# OpenBook.net
KiCad netlist of a schematic drawn in EAGLE
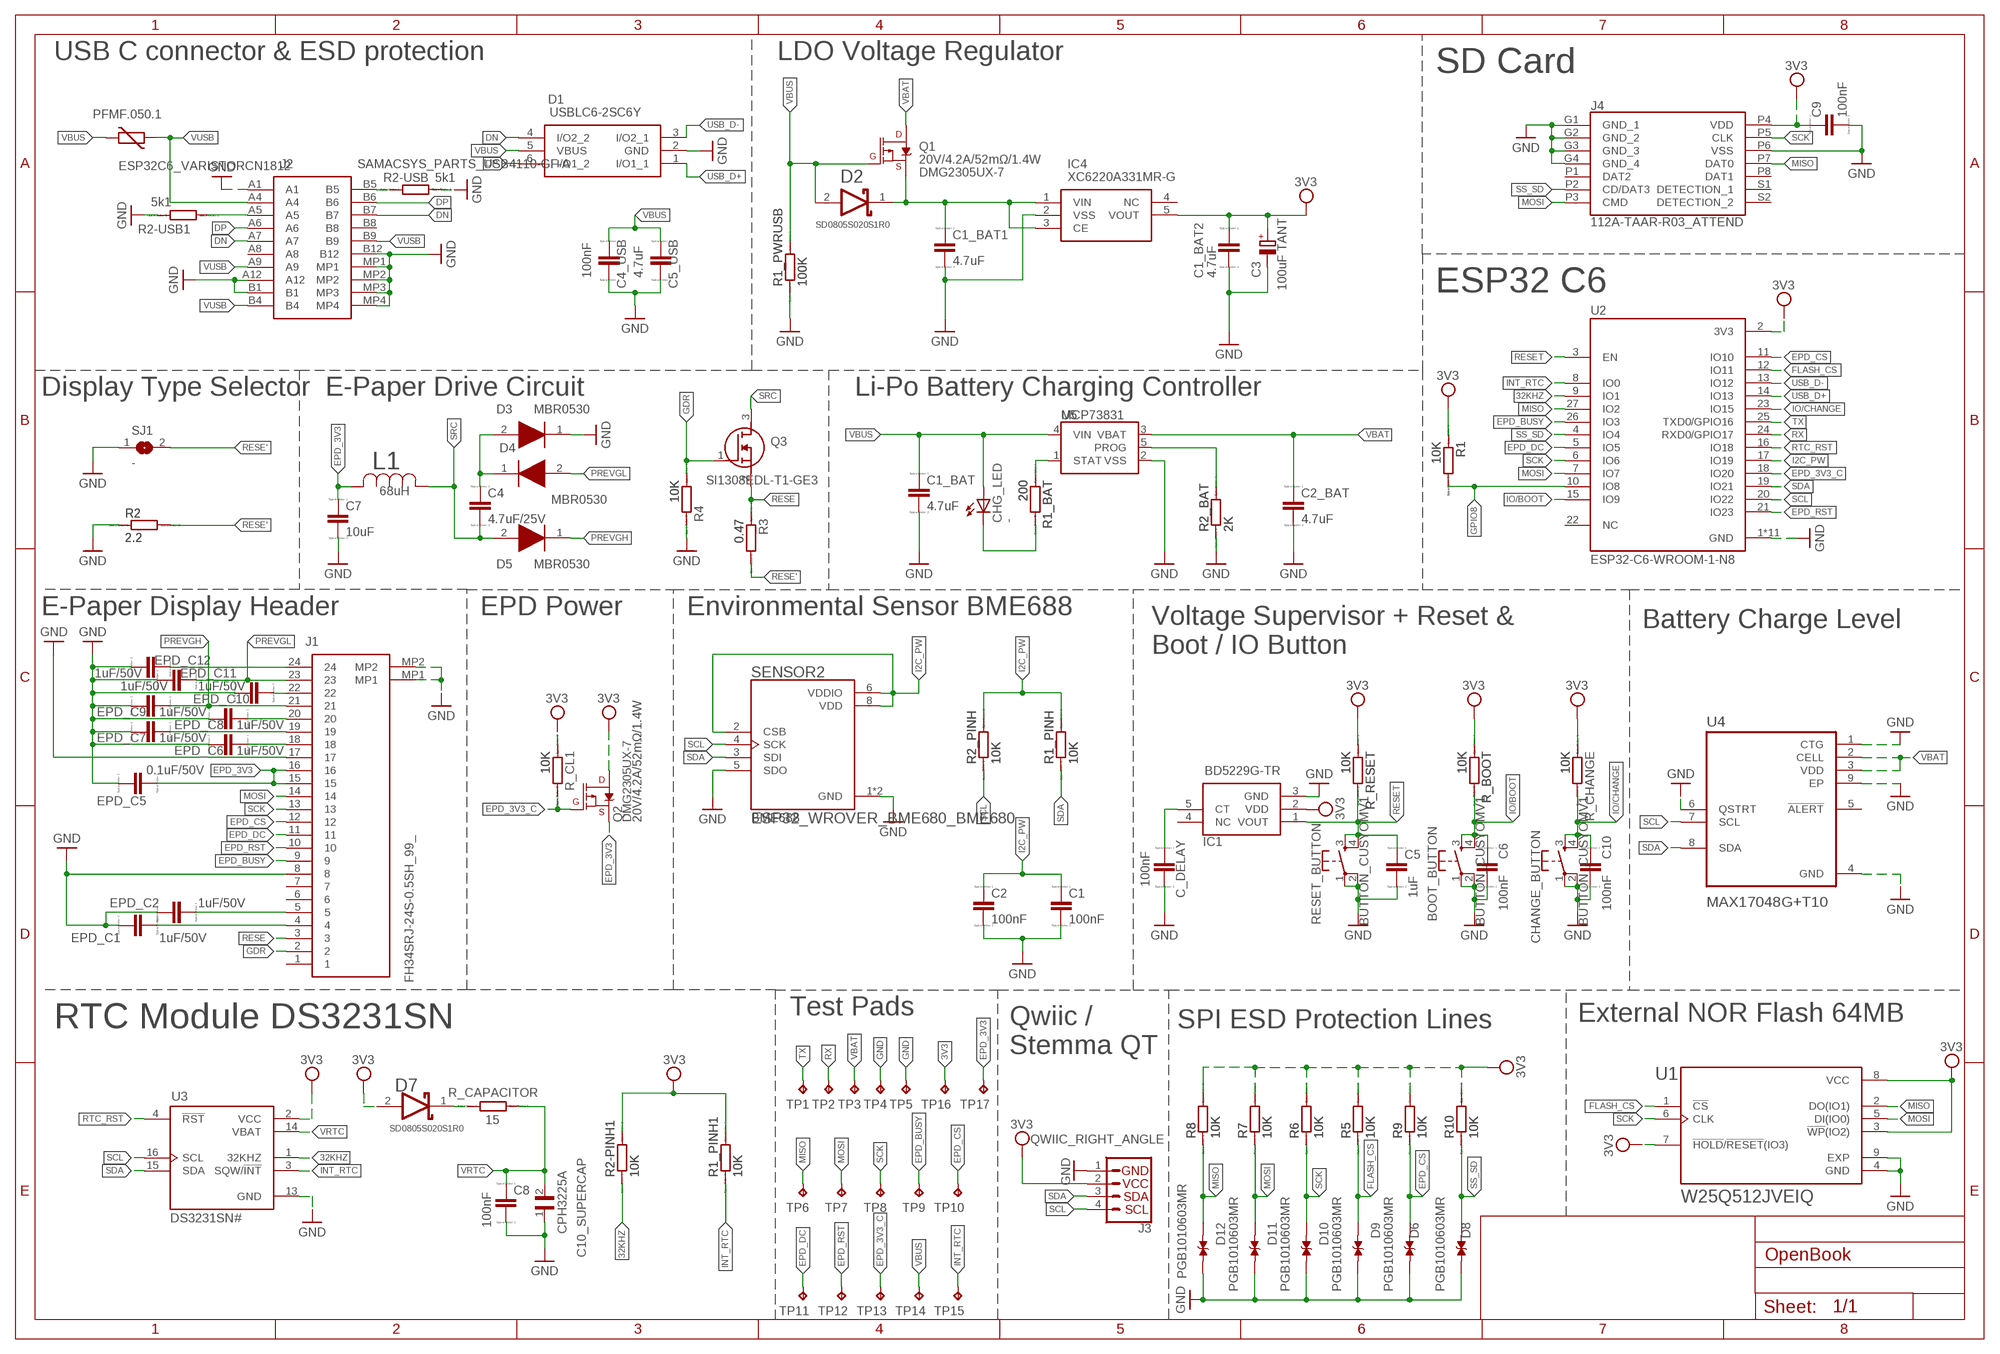
[diagram p0: schematic, sheet 1]

(export (version "E")
  (design (tool "Eeschema 10.0.6"))
  (components
    (comp (ref "BOOT_BUTTON")
      (value "BUTTON_CUSYOMV1")
      (footprint "eagle-import:MYBUTTON")
      (libsource (lib "eagle-import") (part "BUTTON_CUSYOMV1"))
    )
    (comp (ref "C1")
      (value "100nF")
      (footprint "eagle-import:EAGLE-LTSPICE_C0402")
      (libsource (lib "eagle-import") (part "EAGLE-LTSPICE_CC0402"))
    )
    (comp (ref "C1_BAT")
      (value "4.7uF")
      (footprint "eagle-import:EAGLE-LTSPICE_C0402")
      (libsource (lib "eagle-import") (part "EAGLE-LTSPICE_CC0402"))
    )
    (comp (ref "C1_BAT1")
      (value "4.7uF")
      (footprint "eagle-import:EAGLE-LTSPICE_C0402")
      (libsource (lib "eagle-import") (part "EAGLE-LTSPICE_CC0402"))
    )
    (comp (ref "C1_BAT2")
      (value "4.7uF")
      (footprint "eagle-import:EAGLE-LTSPICE_C0402")
      (libsource (lib "eagle-import") (part "EAGLE-LTSPICE_CC0402"))
    )
    (comp (ref "C2")
      (value "100nF")
      (footprint "eagle-import:EAGLE-LTSPICE_C0402")
      (libsource (lib "eagle-import") (part "EAGLE-LTSPICE_CC0402"))
    )
    (comp (ref "C2_BAT")
      (value "4.7uF")
      (footprint "eagle-import:EAGLE-LTSPICE_C0402")
      (libsource (lib "eagle-import") (part "EAGLE-LTSPICE_CC0402"))
    )
    (comp (ref "C3")
      (value "100uF TANT")
      (footprint "eagle-import:RCL_CT3528")
      (libsource (lib "eagle-import") (part "RCL_CPOL-EUCT3528"))
    )
    (comp (ref "C4")
      (value "4.7uF/25V")
      (footprint "eagle-import:EAGLE-LTSPICE_C0402")
      (libsource (lib "eagle-import") (part "EAGLE-LTSPICE_CC0402"))
    )
    (comp (ref "C4_USB")
      (value "100nF")
      (footprint "eagle-import:EAGLE-LTSPICE_C0402")
      (libsource (lib "eagle-import") (part "EAGLE-LTSPICE_CC0402"))
    )
    (comp (ref "C5")
      (value "1uF")
      (footprint "eagle-import:EAGLE-LTSPICE_C0402")
      (libsource (lib "eagle-import") (part "EAGLE-LTSPICE_CC0402"))
    )
    (comp (ref "C5_USB")
      (value "4.7uF")
      (footprint "eagle-import:EAGLE-LTSPICE_C0402")
      (libsource (lib "eagle-import") (part "EAGLE-LTSPICE_CC0402"))
    )
    (comp (ref "C6")
      (value "100nF")
      (footprint "eagle-import:EAGLE-LTSPICE_C0402")
      (libsource (lib "eagle-import") (part "EAGLE-LTSPICE_CC0402"))
    )
    (comp (ref "C7")
      (value "10uF")
      (footprint "eagle-import:EAGLE-LTSPICE_C0402")
      (libsource (lib "eagle-import") (part "EAGLE-LTSPICE_CC0402"))
    )
    (comp (ref "C8")
      (value "100nF")
      (footprint "eagle-import:EAGLE-LTSPICE_C0402")
      (libsource (lib "eagle-import") (part "EAGLE-LTSPICE_CC0402"))
    )
    (comp (ref "C9")
      (value "100nF")
      (footprint "eagle-import:EAGLE-LTSPICE_C0402")
      (libsource (lib "eagle-import") (part "EAGLE-LTSPICE_CC0402"))
    )
    (comp (ref "C10")
      (value "100nF")
      (footprint "eagle-import:EAGLE-LTSPICE_C0402")
      (libsource (lib "eagle-import") (part "EAGLE-LTSPICE_CC0402"))
    )
    (comp (ref "C10_SUPERCAP")
      (value "CPH3225A")
      (footprint "eagle-import:CAPCP3225X100N")
      (fields (field (name "MF") "Seiko Instruments"))
      (libsource (lib "eagle-import") (part "CPH3225A"))
    )
    (comp (ref "CHANGE_BUTTON")
      (value "BUTTON_CUSYOMV1")
      (footprint "eagle-import:MYBUTTON")
      (libsource (lib "eagle-import") (part "BUTTON_CUSYOMV1"))
    )
    (comp (ref "CHG_LED")
      (value "-")
      (footprint "eagle-import:ADAFRUIT_CHIP-LED0603")
      (libsource (lib "eagle-import") (part "ADAFRUIT_LEDCHIP-LED0603"))
    )
    (comp (ref "C_DELAY")
      (value "100nF")
      (footprint "eagle-import:EAGLE-LTSPICE_C0402")
      (libsource (lib "eagle-import") (part "EAGLE-LTSPICE_CC0402"))
    )
    (comp (ref "D1")
      (value "USBLC6-2SC6Y")
      (footprint "eagle-import:SOT95P280X145-6N")
      (fields (field (name "MF") "STMicroelectronics"))
      (libsource (lib "eagle-import") (part "USBLC6-2SC6Y"))
    )
    (comp (ref "D2")
      (value "SD0805S020S1R0")
      (footprint "eagle-import:ESP32_WROVER_AVX---SD0805S020S1R0_AVX_SD0805S020S1R0_0")
      (fields
        (field (name "DIGIKEY_PART_NUMBER") "478-7800-1-ND")
        (field (name "MF") "AVX")
        (field (name "MOUSER_PART_NUMBER") "581-SD0805S020S1R0")
        (field (name "VALUE_COPY") "SD0805S020S1R0")
      )
      (libsource (lib "eagle-import") (part "ESP32_WROVER_AVX---SD0805S020S1R0_AVX_SD0805S020S1R0_0_0AVX_SD0805S020S1R0_0_0"))
    )
    (comp (ref "D3")
      (value "MBR0530")
      (footprint "eagle-import:SOD3716X135N")
      (fields (field (name "MF") "ON Semiconductor"))
      (libsource (lib "eagle-import") (part "MBR0530"))
    )
    (comp (ref "D4")
      (value "MBR0530")
      (footprint "eagle-import:SOD3716X135N")
      (fields (field (name "MF") "ON Semiconductor"))
      (libsource (lib "eagle-import") (part "MBR0530"))
    )
    (comp (ref "D5")
      (value "MBR0530")
      (footprint "eagle-import:SOD3716X135N")
      (fields (field (name "MF") "ON Semiconductor"))
      (libsource (lib "eagle-import") (part "MBR0530"))
    )
    (comp (ref "D6")
      (value "PGB1010603MR")
      (footprint "eagle-import:DIOC1608X36N")
      (fields (field (name "MF") "Littelfuse Inc."))
      (libsource (lib "eagle-import") (part "PGB1010603MR"))
    )
    (comp (ref "D7")
      (value "ESP32_WROVER_AVX---SD0805S020S1R0_AVX_SD0805S020S1R0_0_0AVX_SD0805S020S1R0_0_0")
      (footprint "eagle-import:ESP32_WROVER_AVX---SD0805S020S1R0_AVX_SD0805S020S1R0_0")
      (fields
        (field (name "DIGIKEY_PART_NUMBER") "478-7800-1-ND")
        (field (name "MF") "AVX")
        (field (name "MOUSER_PART_NUMBER") "581-SD0805S020S1R0")
        (field (name "VALUE_COPY") "SD0805S020S1R0")
      )
      (libsource (lib "eagle-import") (part "ESP32_WROVER_AVX---SD0805S020S1R0_AVX_SD0805S020S1R0_0_0AVX_SD0805S020S1R0_0_0"))
    )
    (comp (ref "D8")
      (value "PGB1010603MR")
      (footprint "eagle-import:DIOC1608X36N")
      (fields (field (name "MF") "Littelfuse Inc."))
      (libsource (lib "eagle-import") (part "PGB1010603MR"))
    )
    (comp (ref "D9")
      (value "PGB1010603MR")
      (footprint "eagle-import:DIOC1608X36N")
      (fields (field (name "MF") "Littelfuse Inc."))
      (libsource (lib "eagle-import") (part "PGB1010603MR"))
    )
    (comp (ref "D10")
      (value "PGB1010603MR")
      (footprint "eagle-import:DIOC1608X36N")
      (fields (field (name "MF") "Littelfuse Inc."))
      (libsource (lib "eagle-import") (part "PGB1010603MR"))
    )
    (comp (ref "D11")
      (value "PGB1010603MR")
      (footprint "eagle-import:DIOC1608X36N")
      (fields (field (name "MF") "Littelfuse Inc."))
      (libsource (lib "eagle-import") (part "PGB1010603MR"))
    )
    (comp (ref "D12")
      (value "PGB1010603MR")
      (footprint "eagle-import:DIOC1608X36N")
      (fields (field (name "MF") "Littelfuse Inc."))
      (libsource (lib "eagle-import") (part "PGB1010603MR"))
    )
    (comp (ref "EPD_C1")
      (value "1uF/50V")
      (footprint "eagle-import:EAGLE-LTSPICE_C0402")
      (libsource (lib "eagle-import") (part "EAGLE-LTSPICE_CC0402"))
    )
    (comp (ref "EPD_C2")
      (value "1uF/50V")
      (footprint "eagle-import:EAGLE-LTSPICE_C0402")
      (libsource (lib "eagle-import") (part "EAGLE-LTSPICE_CC0402"))
    )
    (comp (ref "EPD_C5")
      (value "0.1uF/50V")
      (footprint "eagle-import:EAGLE-LTSPICE_C0402")
      (libsource (lib "eagle-import") (part "EAGLE-LTSPICE_CC0402"))
    )
    (comp (ref "EPD_C6")
      (value "1uF/50V")
      (footprint "eagle-import:EAGLE-LTSPICE_C0402")
      (libsource (lib "eagle-import") (part "EAGLE-LTSPICE_CC0402"))
    )
    (comp (ref "EPD_C7")
      (value "1uF/50V")
      (footprint "eagle-import:EAGLE-LTSPICE_C0402")
      (libsource (lib "eagle-import") (part "EAGLE-LTSPICE_CC0402"))
    )
    (comp (ref "EPD_C8")
      (value "1uF/50V")
      (footprint "eagle-import:EAGLE-LTSPICE_C0402")
      (libsource (lib "eagle-import") (part "EAGLE-LTSPICE_CC0402"))
    )
    (comp (ref "EPD_C9")
      (value "1uF/50V")
      (footprint "eagle-import:EAGLE-LTSPICE_C0402")
      (libsource (lib "eagle-import") (part "EAGLE-LTSPICE_CC0402"))
    )
    (comp (ref "EPD_C10")
      (value "1uF/50V")
      (footprint "eagle-import:EAGLE-LTSPICE_C0402")
      (libsource (lib "eagle-import") (part "EAGLE-LTSPICE_CC0402"))
    )
    (comp (ref "EPD_C11")
      (value "1uF/50V")
      (footprint "eagle-import:EAGLE-LTSPICE_C0402")
      (libsource (lib "eagle-import") (part "EAGLE-LTSPICE_CC0402"))
    )
    (comp (ref "EPD_C12")
      (value "1uF/50V")
      (footprint "eagle-import:EAGLE-LTSPICE_C0402")
      (libsource (lib "eagle-import") (part "EAGLE-LTSPICE_CC0402"))
    )
    (comp (ref "IC1")
      (value "BD5229G-TR")
      (footprint "eagle-import:SOT95P280X125-5N")
      (fields (field (name "MOUSER_PART_NUMBER") "755-BD5229G-TR"))
      (libsource (lib "eagle-import") (part "BD5229G-TR"))
    )
    (comp (ref "IC4")
      (value "XC6220A331MR-G")
      (footprint "eagle-import:SOT95P280X120-5N")
      (fields (field (name "MOUSER_PART_NUMBER") "865-XC6220A331MR-G"))
      (libsource (lib "eagle-import") (part "XC6220A331MR-G"))
    )
    (comp (ref "J1")
      (value "FH34SRJ-24S-0.5SH_99_")
      (footprint "eagle-import:FH34SRJ24S05SH99")
      (fields
        (field (name "MANUFACTURER_PART_NUMBER") "FH34SRJ-24S-0.5SH(99)")
        (field (name "MOUSER_PART_NUMBER") "798-FH34SRJ24S05SH99")
      )
      (libsource (lib "eagle-import") (part "FH34SRJ-24S-0.5SH_99_"))
    )
    (comp (ref "J2")
      (value "SAMACSYS_PARTS_USB4110-GF-A")
      (footprint "eagle-import:SAMACSYS_PARTS_USB4110GFA")
      (fields
        (field (name "MANUFACTURER_PART_NUMBER") "USB4110-GF-A")
        (field (name "MOUSER_PART_NUMBER") "640-USB4110-GF-A")
      )
      (libsource (lib "eagle-import") (part "SAMACSYS_PARTS_USB4110-GF-A"))
    )
    (comp (ref "J3")
      (value "QWIIC_RIGHT_ANGLE")
      (footprint "eagle-import:JST04_1MM_RA")
      (libsource (lib "eagle-import") (part "QWIIC_CONNECTORJS-1MM"))
    )
    (comp (ref "J4")
      (value "112A-TAAR-R03_ATTEND")
      (footprint "eagle-import:112ATAARR03ATTEND")
      (fields (field (name "MANUFACTURER_PART_NUMBER") "112A-TAAR-R03 ATTEND"))
      (libsource (lib "eagle-import") (part "112A-TAAR-R03_ATTEND"))
    )
    (comp (ref "L1")
      (value "68uH")
      (footprint "eagle-import:IND_4828-WE-TPC_WRE")
      (fields
        (field (name "MANUFACTURER_PART_NUMBER") "744043680")
        (field (name "COPYRIGHT") "Copyright (C) 2024 Ultra Librarian. All rights reserved.")
      )
      (libsource (lib "eagle-import") (part "744043680IND_4828-WE-TPC_WRE"))
    )
    (comp (ref "PFMF.050.1")
      (value "ESP32C6_VARISTORCN1812")
      (footprint "eagle-import:ESP32C6_VARISTOR_CT_CN1812")
      (libsource (lib "eagle-import") (part "ESP32C6_VARISTORCN1812"))
    )
    (comp (ref "Q1")
      (value "20V/4.2A/52mΩ/1.4W")
      (footprint "eagle-import:ESP32_WROVER_SPARKFUN-DISCRETESEMI_SOT23-3")
      (fields (field (name "COMP_NAME") "DMG2305UX-7"))
      (libsource (lib "eagle-import") (part "ESP32_WROVER_SPARKFUN-DISCRETESEMI_MOSFET_PCH-DMG2305UX-7"))
    )
    (comp (ref "Q2")
      (value "20V/4.2A/52mΩ/1.4W")
      (footprint "eagle-import:ESP32_WROVER_SPARKFUN-DISCRETESEMI_SOT23-3")
      (fields (field (name "MP") "DMG2305UX-7"))
      (libsource (lib "eagle-import") (part "ESP32_WROVER_SPARKFUN-DISCRETESEMI_MOSFET_PCH-DMG2305UX-7"))
    )
    (comp (ref "Q3")
      (value "SI1308EDL-T1-GE3")
      (footprint "eagle-import:SOT65P210X110-3N")
      (fields (field (name "MF") "Vishay Siliconix"))
      (libsource (lib "eagle-import") (part "SI1308EDL-T1-GE3"))
    )
    (comp (ref "R1")
      (value "10K")
      (footprint "eagle-import:ESP32_WROVER_EAGLE-LTSPICE_R0402")
      (libsource (lib "eagle-import") (part "ESP32_WROVER_EAGLE-LTSPICE_RR0402"))
    )
    (comp (ref "R1_BAT")
      (value "200")
      (footprint "eagle-import:ESP32_WROVER_EAGLE-LTSPICE_R0402")
      (libsource (lib "eagle-import") (part "ESP32_WROVER_EAGLE-LTSPICE_RR0402"))
    )
    (comp (ref "R1_PINH")
      (value "10K")
      (footprint "eagle-import:ESP32_WROVER_EAGLE-LTSPICE_R0402")
      (libsource (lib "eagle-import") (part "ESP32_WROVER_EAGLE-LTSPICE_RR0402"))
    )
    (comp (ref "R1_PINH1")
      (value "10K")
      (footprint "eagle-import:ESP32_WROVER_EAGLE-LTSPICE_R0402")
      (libsource (lib "eagle-import") (part "ESP32_WROVER_EAGLE-LTSPICE_RR0402"))
    )
    (comp (ref "R1_PWRUSB")
      (value "100K")
      (footprint "eagle-import:ESP32_WROVER_EAGLE-LTSPICE_R0402")
      (libsource (lib "eagle-import") (part "ESP32_WROVER_EAGLE-LTSPICE_RR0402"))
    )
    (comp (ref "R2")
      (value "2.2")
      (footprint "eagle-import:ESP32_WROVER_EAGLE-LTSPICE_R0402")
      (libsource (lib "eagle-import") (part "ESP32_WROVER_EAGLE-LTSPICE_RR0402"))
    )
    (comp (ref "R2-PINH1")
      (value "10K")
      (footprint "eagle-import:ESP32_WROVER_EAGLE-LTSPICE_R0402")
      (libsource (lib "eagle-import") (part "ESP32_WROVER_EAGLE-LTSPICE_RR0402"))
    )
    (comp (ref "R2-USB")
      (value "5k1")
      (footprint "eagle-import:ESP32_WROVER_EAGLE-LTSPICE_R0402")
      (libsource (lib "eagle-import") (part "ESP32_WROVER_EAGLE-LTSPICE_RR0402"))
    )
    (comp (ref "R2-USB1")
      (value "5k1")
      (footprint "eagle-import:ESP32_WROVER_EAGLE-LTSPICE_R0402")
      (libsource (lib "eagle-import") (part "ESP32_WROVER_EAGLE-LTSPICE_RR0402"))
    )
    (comp (ref "R2_BAT")
      (value "2K")
      (footprint "eagle-import:ESP32_WROVER_EAGLE-LTSPICE_R0402")
      (libsource (lib "eagle-import") (part "ESP32_WROVER_EAGLE-LTSPICE_RR0402"))
    )
    (comp (ref "R2_PINH")
      (value "10K")
      (footprint "eagle-import:ESP32_WROVER_EAGLE-LTSPICE_R0402")
      (libsource (lib "eagle-import") (part "ESP32_WROVER_EAGLE-LTSPICE_RR0402"))
    )
    (comp (ref "R3")
      (value "0.47")
      (footprint "eagle-import:ESP32_WROVER_EAGLE-LTSPICE_R0402")
      (libsource (lib "eagle-import") (part "ESP32_WROVER_EAGLE-LTSPICE_RR0402"))
    )
    (comp (ref "R4")
      (value "10K")
      (footprint "eagle-import:ESP32_WROVER_EAGLE-LTSPICE_R0402")
      (libsource (lib "eagle-import") (part "ESP32_WROVER_EAGLE-LTSPICE_RR0402"))
    )
    (comp (ref "R5")
      (value "10K")
      (footprint "eagle-import:ESP32_WROVER_EAGLE-LTSPICE_R0402")
      (libsource (lib "eagle-import") (part "ESP32_WROVER_EAGLE-LTSPICE_RR0402"))
    )
    (comp (ref "R6")
      (value "10K")
      (footprint "eagle-import:ESP32_WROVER_EAGLE-LTSPICE_R0402")
      (libsource (lib "eagle-import") (part "ESP32_WROVER_EAGLE-LTSPICE_RR0402"))
    )
    (comp (ref "R7")
      (value "10K")
      (footprint "eagle-import:ESP32_WROVER_EAGLE-LTSPICE_R0402")
      (libsource (lib "eagle-import") (part "ESP32_WROVER_EAGLE-LTSPICE_RR0402"))
    )
    (comp (ref "R8")
      (value "10K")
      (footprint "eagle-import:ESP32_WROVER_EAGLE-LTSPICE_R0402")
      (libsource (lib "eagle-import") (part "ESP32_WROVER_EAGLE-LTSPICE_RR0402"))
    )
    (comp (ref "R9")
      (value "10K")
      (footprint "eagle-import:ESP32_WROVER_EAGLE-LTSPICE_R0402")
      (libsource (lib "eagle-import") (part "ESP32_WROVER_EAGLE-LTSPICE_RR0402"))
    )
    (comp (ref "R10")
      (value "10K")
      (footprint "eagle-import:ESP32_WROVER_EAGLE-LTSPICE_R0402")
      (libsource (lib "eagle-import") (part "ESP32_WROVER_EAGLE-LTSPICE_RR0402"))
    )
    (comp (ref "RESET_BUTTON")
      (value "BUTTON_CUSYOMV1")
      (footprint "eagle-import:MYBUTTON")
      (libsource (lib "eagle-import") (part "BUTTON_CUSYOMV1"))
    )
    (comp (ref "R_BOOT")
      (value "10K")
      (footprint "eagle-import:ESP32_WROVER_EAGLE-LTSPICE_R0402")
      (libsource (lib "eagle-import") (part "ESP32_WROVER_EAGLE-LTSPICE_RR0402"))
    )
    (comp (ref "R_CAPACITOR")
      (value "15")
      (footprint "eagle-import:ESP32_WROVER_EAGLE-LTSPICE_R0402")
      (libsource (lib "eagle-import") (part "ESP32_WROVER_EAGLE-LTSPICE_RR0402"))
    )
    (comp (ref "R_CHANGE")
      (value "10K")
      (footprint "eagle-import:ESP32_WROVER_EAGLE-LTSPICE_R0402")
      (libsource (lib "eagle-import") (part "ESP32_WROVER_EAGLE-LTSPICE_RR0402"))
    )
    (comp (ref "R_CL1")
      (value "10K")
      (footprint "eagle-import:ESP32_WROVER_EAGLE-LTSPICE_R0402")
      (libsource (lib "eagle-import") (part "ESP32_WROVER_EAGLE-LTSPICE_RR0402"))
    )
    (comp (ref "R_RESET")
      (value "10K")
      (footprint "eagle-import:ESP32_WROVER_EAGLE-LTSPICE_R0402")
      (libsource (lib "eagle-import") (part "ESP32_WROVER_EAGLE-LTSPICE_RR0402"))
    )
    (comp (ref "SENSOR2")
      (value "ESP32_WROVER_BME680_BME680")
      (footprint "eagle-import:ESP32_WROVER_BME680_PSON80P300X300X100-8N")
      (fields
        (field (name "MF") "Bosch Sensortec")
        (field (name "MP") "BME680")
        (field (name "NEW_MP") "BME688")
      )
      (libsource (lib "eagle-import") (part "ESP32_WROVER_BME680_BME680"))
    )
    (comp (ref "SJ1") (value "-") (footprint "eagle-import:SJ") (libsource (lib "eagle-import") (part "SJ")))
    (comp (ref "TP1")
      (value "TPTP20R")
      (footprint "eagle-import:TP20R")
      (libsource (lib "eagle-import") (part "TPTP20R"))
    )
    (comp (ref "TP2")
      (value "TPTP20R")
      (footprint "eagle-import:TP20R")
      (libsource (lib "eagle-import") (part "TPTP20R"))
    )
    (comp (ref "TP3")
      (value "TPTP20R")
      (footprint "eagle-import:TP20R")
      (libsource (lib "eagle-import") (part "TPTP20R"))
    )
    (comp (ref "TP4")
      (value "TPTP20R")
      (footprint "eagle-import:TP20R")
      (libsource (lib "eagle-import") (part "TPTP20R"))
    )
    (comp (ref "TP5")
      (value "TPTP20R")
      (footprint "eagle-import:TP20R")
      (libsource (lib "eagle-import") (part "TPTP20R"))
    )
    (comp (ref "TP6")
      (value "TPTP20R")
      (footprint "eagle-import:TP20R")
      (libsource (lib "eagle-import") (part "TPTP20R"))
    )
    (comp (ref "TP7")
      (value "TPTP20R")
      (footprint "eagle-import:TP20R")
      (libsource (lib "eagle-import") (part "TPTP20R"))
    )
    (comp (ref "TP8")
      (value "TPTP20R")
      (footprint "eagle-import:TP20R")
      (libsource (lib "eagle-import") (part "TPTP20R"))
    )
    (comp (ref "TP9")
      (value "TPTP20R")
      (footprint "eagle-import:TP20R")
      (libsource (lib "eagle-import") (part "TPTP20R"))
    )
    (comp (ref "TP10")
      (value "TPTP20R")
      (footprint "eagle-import:TP20R")
      (libsource (lib "eagle-import") (part "TPTP20R"))
    )
    (comp (ref "TP11")
      (value "TPTP20R")
      (footprint "eagle-import:TP20R")
      (libsource (lib "eagle-import") (part "TPTP20R"))
    )
    (comp (ref "TP12")
      (value "TPTP20R")
      (footprint "eagle-import:TP20R")
      (libsource (lib "eagle-import") (part "TPTP20R"))
    )
    (comp (ref "TP13")
      (value "TPTP20R")
      (footprint "eagle-import:TP20R")
      (libsource (lib "eagle-import") (part "TPTP20R"))
    )
    (comp (ref "TP14")
      (value "TPTP20R")
      (footprint "eagle-import:TP20R")
      (libsource (lib "eagle-import") (part "TPTP20R"))
    )
    (comp (ref "TP15")
      (value "TPTP20R")
      (footprint "eagle-import:TP20R")
      (libsource (lib "eagle-import") (part "TPTP20R"))
    )
    (comp (ref "TP16")
      (value "TPTP20R")
      (footprint "eagle-import:TP20R")
      (libsource (lib "eagle-import") (part "TPTP20R"))
    )
    (comp (ref "TP17")
      (value "TPTP20R")
      (footprint "eagle-import:TP20R")
      (libsource (lib "eagle-import") (part "TPTP20R"))
    )
    (comp (ref "U1")
      (value "W25Q512JVEIQ")
      (footprint "eagle-import:SON127P600X800X80-9N")
      (fields (field (name "MF") "Winbond Electronics"))
      (libsource (lib "eagle-import") (part "W25Q512JVEIQ"))
    )
    (comp (ref "U2")
      (value "ESP32-C6-WROOM-1-N8")
      (footprint "eagle-import:XCVR_ESP32-C6-WROOM-1-N8")
      (fields (field (name "MF") "Espressif Systems"))
      (libsource (lib "eagle-import") (part "ESP32-C6-WROOM-1-N8"))
    )
    (comp (ref "U3")
      (value "DS3231SN#")
      (footprint "eagle-import:SOIC127P1032X265-16N")
      (fields (field (name "MF") "Analog Devices"))
      (libsource (lib "eagle-import") (part "DS3231SN#"))
    )
    (comp (ref "U4")
      (value "MAX17048G+T10")
      (footprint "eagle-import:SON50P200X200X80-9N")
      (fields (field (name "MF") "Analog Devices"))
      (libsource (lib "eagle-import") (part "MAX17048G+T10"))
    )
    (comp (ref "U5")
      (value "MCP73831")
      (footprint "eagle-import:ESP32_WROVER_SPARKFUN-IC-POWER_SOT23-5")
      (libsource (lib "eagle-import") (part "ESP32_WROVER_SPARKFUN-IC-POWER_MCP73831"))
    )
  )
  (nets
    (net (code "1") (name "3V3") (class "Default")
      (node (ref "C1_BAT2") (pin "1") (pinfunction "1_1") (pintype "passive"))
      (node (ref "C3") (pin "+") (pinfunction "+_+") (pintype "passive"))
      (node (ref "C9") (pin "1") (pinfunction "1_1") (pintype "passive"))
      (node (ref "D7") (pin "2") (pinfunction "ANODE_2") (pintype "bidirectional"))
      (node (ref "IC1") (pin "2") (pinfunction "VDD_2") (pintype "bidirectional"))
      (node (ref "IC4") (pin "5") (pinfunction "VOUT_5") (pintype "bidirectional"))
      (node (ref "J3") (pin "2") (pinfunction "2_2") (pintype "power_in"))
      (node (ref "J4") (pin "P4") (pinfunction "VDD_P4") (pintype "bidirectional"))
      (node (ref "Q2") (pin "3") (pinfunction "D_3") (pintype "bidirectional"))
      (node (ref "R1") (pin "1") (pinfunction "1_1") (pintype "passive"))
      (node (ref "R10") (pin "2") (pinfunction "2_2") (pintype "passive"))
      (node (ref "R1_PINH1") (pin "2") (pinfunction "2_2") (pintype "passive"))
      (node (ref "R2-PINH1") (pin "2") (pinfunction "2_2") (pintype "passive"))
      (node (ref "R5") (pin "2") (pinfunction "2_2") (pintype "passive"))
      (node (ref "R6") (pin "2") (pinfunction "2_2") (pintype "passive"))
      (node (ref "R7") (pin "2") (pinfunction "2_2") (pintype "passive"))
      (node (ref "R8") (pin "2") (pinfunction "2_2") (pintype "passive"))
      (node (ref "R9") (pin "2") (pinfunction "2_2") (pintype "passive"))
      (node (ref "R_BOOT") (pin "1") (pinfunction "1_1") (pintype "passive"))
      (node (ref "R_CHANGE") (pin "1") (pinfunction "1_1") (pintype "passive"))
      (node (ref "R_CL1") (pin "1") (pinfunction "1_1") (pintype "passive"))
      (node (ref "R_RESET") (pin "1") (pinfunction "1_1") (pintype "passive"))
      (node (ref "TP16") (pin "TP") (pinfunction "TP_TP") (pintype "input"))
      (node (ref "U1") (pin "3") (pinfunction "~{WP}(IO2)_3") (pintype "bidirectional"))
      (node (ref "U1") (pin "7") (pinfunction "~{HOLD}/~{RESET}(IO3)_7") (pintype "bidirectional"))
      (node (ref "U1") (pin "8") (pinfunction "VCC_8") (pintype "power_in"))
      (node (ref "U2") (pin "2") (pinfunction "3V3_2") (pintype "power_in"))
      (node (ref "U3") (pin "2") (pinfunction "VCC_2") (pintype "power_in"))
    )
    (net (code "2") (name "32KHZ") (class "Default")
      (node (ref "R2-PINH1") (pin "1") (pinfunction "1_1") (pintype "passive"))
      (node (ref "U2") (pin "9") (pinfunction "IO1_9") (pintype "bidirectional"))
      (node (ref "U3") (pin "1") (pinfunction "32KHZ_1") (pintype "output"))
    )
    (net (code "3") (name "DN") (class "Default")
      (node (ref "D1") (pin "4") (pinfunction "I/O2_2_4") (pintype "bidirectional"))
      (node (ref "J2") (pin "A7") (pinfunction "A7_A7") (pintype "bidirectional"))
      (node (ref "J2") (pin "B7") (pinfunction "B7_B7") (pintype "bidirectional"))
    )
    (net (code "4") (name "DP") (class "Default")
      (node (ref "D1") (pin "6") (pinfunction "I/O1_2_6") (pintype "bidirectional"))
      (node (ref "J2") (pin "A6") (pinfunction "A6_A6") (pintype "bidirectional"))
      (node (ref "J2") (pin "B6") (pinfunction "B6_B6") (pintype "bidirectional"))
    )
    (net (code "5") (name "EPD_3V3") (class "Default")
      (node (ref "C7") (pin "1") (pinfunction "1_1") (pintype "passive"))
      (node (ref "EPD_C5") (pin "1") (pinfunction "1_1") (pintype "passive"))
      (node (ref "J1") (pin "15") (pinfunction "15_15") (pintype "bidirectional"))
      (node (ref "J1") (pin "16") (pinfunction "16_16") (pintype "bidirectional"))
      (node (ref "L1") (pin "2") (pinfunction "2_2") (pintype "passive"))
      (node (ref "Q2") (pin "2") (pinfunction "S_2") (pintype "bidirectional"))
      (node (ref "TP17") (pin "TP") (pinfunction "TP_TP") (pintype "input"))
    )
    (net (code "6") (name "EPD_3V3_C") (class "Default")
      (node (ref "Q2") (pin "1") (pinfunction "G_1") (pintype "bidirectional"))
      (node (ref "R_CL1") (pin "2") (pinfunction "2_2") (pintype "passive"))
      (node (ref "TP13") (pin "TP") (pinfunction "TP_TP") (pintype "input"))
      (node (ref "U2") (pin "18") (pinfunction "IO20_18") (pintype "bidirectional"))
    )
    (net (code "7") (name "EPD_BUSY") (class "Default")
      (node (ref "J1") (pin "9") (pinfunction "9_9") (pintype "bidirectional"))
      (node (ref "TP9") (pin "TP") (pinfunction "TP_TP") (pintype "input"))
      (node (ref "U2") (pin "26") (pinfunction "IO3_26") (pintype "bidirectional"))
    )
    (net (code "8") (name "EPD_CS") (class "Default")
      (node (ref "D6") (pin "1") (pinfunction "1_1") (pintype "passive"))
      (node (ref "J1") (pin "12") (pinfunction "12_12") (pintype "bidirectional"))
      (node (ref "R9") (pin "1") (pinfunction "1_1") (pintype "passive"))
      (node (ref "TP10") (pin "TP") (pinfunction "TP_TP") (pintype "input"))
      (node (ref "U2") (pin "11") (pinfunction "IO10_11") (pintype "bidirectional"))
    )
    (net (code "9") (name "EPD_DC") (class "Default")
      (node (ref "J1") (pin "11") (pinfunction "11_11") (pintype "bidirectional"))
      (node (ref "TP11") (pin "TP") (pinfunction "TP_TP") (pintype "input"))
      (node (ref "U2") (pin "5") (pinfunction "IO5_5") (pintype "bidirectional"))
    )
    (net (code "10") (name "EPD_RST") (class "Default")
      (node (ref "J1") (pin "10") (pinfunction "10_10") (pintype "bidirectional"))
      (node (ref "TP12") (pin "TP") (pinfunction "TP_TP") (pintype "input"))
      (node (ref "U2") (pin "21") (pinfunction "IO23_21") (pintype "bidirectional"))
    )
    (net (code "11") (name "FLASH_CS") (class "Default")
      (node (ref "D9") (pin "1") (pinfunction "1_1") (pintype "passive"))
      (node (ref "R5") (pin "1") (pinfunction "1_1") (pintype "passive"))
      (node (ref "U1") (pin "1") (pinfunction "~{CS}_1") (pintype "input"))
      (node (ref "U2") (pin "12") (pinfunction "IO11_12") (pintype "bidirectional"))
    )
    (net (code "12") (name "GDR") (class "Default")
      (node (ref "J1") (pin "2") (pinfunction "2_2") (pintype "bidirectional"))
      (node (ref "Q3") (pin "1") (pinfunction "G_1") (pintype "bidirectional"))
      (node (ref "R4") (pin "1") (pinfunction "1_1") (pintype "passive"))
    )
    (net (code "13") (name "GND") (class "Default")
      (node (ref "BOOT_BUTTON") (pin "1") (pinfunction "1_1") (pintype "passive"))
      (node (ref "BOOT_BUTTON") (pin "2") (pinfunction "2_2") (pintype "passive"))
      (node (ref "C1") (pin "2") (pinfunction "2_2") (pintype "passive"))
      (node (ref "C10") (pin "2") (pinfunction "2_2") (pintype "passive"))
      (node (ref "C10_SUPERCAP") (pin "1") (pinfunction "1_1") (pintype "passive"))
      (node (ref "C1_BAT") (pin "2") (pinfunction "2_2") (pintype "passive"))
      (node (ref "C1_BAT1") (pin "2") (pinfunction "2_2") (pintype "passive"))
      (node (ref "C1_BAT2") (pin "2") (pinfunction "2_2") (pintype "passive"))
      (node (ref "C2") (pin "2") (pinfunction "2_2") (pintype "passive"))
      (node (ref "C2_BAT") (pin "2") (pinfunction "2_2") (pintype "passive"))
      (node (ref "C3") (pin "-") (pinfunction "-_-") (pintype "passive"))
      (node (ref "C4_USB") (pin "2") (pinfunction "2_2") (pintype "passive"))
      (node (ref "C5") (pin "2") (pinfunction "2_2") (pintype "passive"))
      (node (ref "C5_USB") (pin "2") (pinfunction "2_2") (pintype "passive"))
      (node (ref "C6") (pin "2") (pinfunction "2_2") (pintype "passive"))
      (node (ref "C7") (pin "2") (pinfunction "2_2") (pintype "passive"))
      (node (ref "C8") (pin "2") (pinfunction "2_2") (pintype "passive"))
      (node (ref "C9") (pin "2") (pinfunction "2_2") (pintype "passive"))
      (node (ref "CHANGE_BUTTON") (pin "1") (pinfunction "1_1") (pintype "passive"))
      (node (ref "CHANGE_BUTTON") (pin "2") (pinfunction "2_2") (pintype "passive"))
      (node (ref "C_DELAY") (pin "2") (pinfunction "2_2") (pintype "passive"))
      (node (ref "D1") (pin "2") (pinfunction "GND_2") (pintype "bidirectional"))
      (node (ref "D10") (pin "2") (pinfunction "2_2") (pintype "passive"))
      (node (ref "D11") (pin "2") (pinfunction "2_2") (pintype "passive"))
      (node (ref "D12") (pin "2") (pinfunction "2_2") (pintype "passive"))
      (node (ref "D3") (pin "1") (pinfunction "K_1") (pintype "bidirectional"))
      (node (ref "D6") (pin "2") (pinfunction "2_2") (pintype "passive"))
      (node (ref "D8") (pin "2") (pinfunction "2_2") (pintype "passive"))
      (node (ref "D9") (pin "2") (pinfunction "2_2") (pintype "passive"))
      (node (ref "EPD_C1") (pin "2") (pinfunction "2_2") (pintype "passive"))
      (node (ref "EPD_C10") (pin "2") (pinfunction "2_2") (pintype "passive"))
      (node (ref "EPD_C11") (pin "2") (pinfunction "2_2") (pintype "passive"))
      (node (ref "EPD_C12") (pin "2") (pinfunction "2_2") (pintype "passive"))
      (node (ref "EPD_C2") (pin "2") (pinfunction "2_2") (pintype "passive"))
      (node (ref "EPD_C5") (pin "2") (pinfunction "2_2") (pintype "passive"))
      (node (ref "EPD_C6") (pin "2") (pinfunction "2_2") (pintype "passive"))
      (node (ref "EPD_C7") (pin "2") (pinfunction "2_2") (pintype "passive"))
      (node (ref "EPD_C8") (pin "2") (pinfunction "2_2") (pintype "passive"))
      (node (ref "EPD_C9") (pin "2") (pinfunction "2_2") (pintype "passive"))
      (node (ref "IC1") (pin "3") (pinfunction "GND_3") (pintype "bidirectional"))
      (node (ref "IC4") (pin "2") (pinfunction "VSS_2") (pintype "bidirectional"))
      (node (ref "J1") (pin "17") (pinfunction "17_17") (pintype "bidirectional"))
      (node (ref "J1") (pin "8") (pinfunction "8_8") (pintype "bidirectional"))
      (node (ref "J1") (pin "MP1") (pinfunction "MP1_MP1") (pintype "bidirectional"))
      (node (ref "J1") (pin "MP2") (pinfunction "MP2_MP2") (pintype "bidirectional"))
      (node (ref "J2") (pin "A1") (pinfunction "A1_A1") (pintype "bidirectional"))
      (node (ref "J2") (pin "A12") (pinfunction "A12_A12") (pintype "bidirectional"))
      (node (ref "J2") (pin "B1") (pinfunction "B1_B1") (pintype "bidirectional"))
      (node (ref "J2") (pin "B12") (pinfunction "B12_B12") (pintype "bidirectional"))
      (node (ref "J2") (pin "MP1") (pinfunction "MP1_MP1") (pintype "bidirectional"))
      (node (ref "J2") (pin "MP2") (pinfunction "MP2_MP2") (pintype "bidirectional"))
      (node (ref "J2") (pin "MP3") (pinfunction "MP3_MP3") (pintype "bidirectional"))
      (node (ref "J2") (pin "MP4") (pinfunction "MP4_MP4") (pintype "bidirectional"))
      (node (ref "J3") (pin "1") (pinfunction "1_1") (pintype "power_in"))
      (node (ref "J4") (pin "G1") (pinfunction "GND_1_G1") (pintype "bidirectional"))
      (node (ref "J4") (pin "G2") (pinfunction "GND_2_G2") (pintype "bidirectional"))
      (node (ref "J4") (pin "G3") (pinfunction "GND_3_G3") (pintype "bidirectional"))
      (node (ref "J4") (pin "G4") (pinfunction "GND_4_G4") (pintype "bidirectional"))
      (node (ref "J4") (pin "P6") (pinfunction "VSS_P6") (pintype "bidirectional"))
      (node (ref "R1_PWRUSB") (pin "1") (pinfunction "1_1") (pintype "passive"))
      (node (ref "R2") (pin "1") (pinfunction "1_1") (pintype "passive"))
      (node (ref "R2-USB") (pin "2") (pinfunction "2_2") (pintype "passive"))
      (node (ref "R2-USB1") (pin "1") (pinfunction "1_1") (pintype "passive"))
      (node (ref "R2_BAT") (pin "1") (pinfunction "1_1") (pintype "passive"))
      (node (ref "R4") (pin "2") (pinfunction "2_2") (pintype "passive"))
      (node (ref "RESET_BUTTON") (pin "1") (pinfunction "1_1") (pintype "passive"))
      (node (ref "RESET_BUTTON") (pin "2") (pinfunction "2_2") (pintype "passive"))
      (node (ref "SENSOR2") (pin "1") (pinfunction "GND_1") (pintype "power_in"))
      (node (ref "SENSOR2") (pin "5") (pinfunction "SDO_5") (pintype "bidirectional"))
      (node (ref "SENSOR2") (pin "7") (pinfunction "GND_7") (pintype "power_in"))
      (node (ref "SJ1") (pin "1") (pinfunction "1_1") (pintype "passive"))
      (node (ref "TP4") (pin "TP") (pinfunction "TP_TP") (pintype "input"))
      (node (ref "TP5") (pin "TP") (pinfunction "TP_TP") (pintype "input"))
      (node (ref "U1") (pin "4") (pinfunction "GND_4") (pintype "power_in"))
      (node (ref "U1") (pin "9") (pinfunction "EXP_9") (pintype "passive"))
      (node (ref "U2") (pin "1") (pinfunction "GND_1") (pintype "power_in"))
      (node (ref "U2") (pin "28") (pinfunction "GND_28") (pintype "power_in"))
      (node (ref "U2") (pin "29_1") (pinfunction "GND_29_1") (pintype "power_in"))
      (node (ref "U2") (pin "29_2") (pinfunction "GND_29_2") (pintype "power_in"))
      (node (ref "U2") (pin "29_3") (pinfunction "GND_29_3") (pintype "power_in"))
      (node (ref "U2") (pin "29_4") (pinfunction "GND_29_4") (pintype "power_in"))
      (node (ref "U2") (pin "29_5") (pinfunction "GND_29_5") (pintype "power_in"))
      (node (ref "U2") (pin "29_6") (pinfunction "GND_29_6") (pintype "power_in"))
      (node (ref "U2") (pin "29_7") (pinfunction "GND_29_7") (pintype "power_in"))
      (node (ref "U2") (pin "29_8") (pinfunction "GND_29_8") (pintype "power_in"))
      (node (ref "U2") (pin "29_9") (pinfunction "GND_29_9") (pintype "power_in"))
      (node (ref "U3") (pin "13") (pinfunction "GND_13") (pintype "power_in"))
      (node (ref "U4") (pin "1") (pinfunction "CTG_1") (pintype "power_in"))
      (node (ref "U4") (pin "4") (pinfunction "GND_4") (pintype "power_in"))
      (node (ref "U4") (pin "6") (pinfunction "QSTRT_6") (pintype "input"))
      (node (ref "U4") (pin "9") (pinfunction "EP_9") (pintype "power_in"))
      (node (ref "U5") (pin "2") (pinfunction "VSS_2") (pintype "power_in"))
    )
    (net (code "14") (name "GPIO8") (class "Default")
      (node (ref "R1") (pin "2") (pinfunction "2_2") (pintype "passive"))
      (node (ref "U2") (pin "10") (pinfunction "IO8_10") (pintype "bidirectional"))
    )
    (net (code "15") (name "I2C_PW") (class "Default")
      (node (ref "C1") (pin "1") (pinfunction "1_1") (pintype "passive"))
      (node (ref "C2") (pin "1") (pinfunction "1_1") (pintype "passive"))
      (node (ref "R1_PINH") (pin "2") (pinfunction "2_2") (pintype "passive"))
      (node (ref "R2_PINH") (pin "2") (pinfunction "2_2") (pintype "passive"))
      (node (ref "SENSOR2") (pin "2") (pinfunction "CSB_2") (pintype "input"))
      (node (ref "SENSOR2") (pin "6") (pinfunction "VDDIO_6") (pintype "power_in"))
      (node (ref "SENSOR2") (pin "8") (pinfunction "VDD_8") (pintype "power_in"))
      (node (ref "U2") (pin "17") (pinfunction "IO19_17") (pintype "bidirectional"))
    )
    (net (code "16") (name "INT_RTC") (class "Default")
      (node (ref "R1_PINH1") (pin "1") (pinfunction "1_1") (pintype "passive"))
      (node (ref "TP15") (pin "TP") (pinfunction "TP_TP") (pintype "input"))
      (node (ref "U2") (pin "8") (pinfunction "IO0_8") (pintype "bidirectional"))
      (node (ref "U3") (pin "3") (pinfunction "SQW/~{INT}_3") (pintype "output"))
    )
    (net (code "17") (name "IO{slash}BOOT") (class "Default")
      (node (ref "BOOT_BUTTON") (pin "3") (pinfunction "3_3") (pintype "passive"))
      (node (ref "BOOT_BUTTON") (pin "4") (pinfunction "4_4") (pintype "passive"))
      (node (ref "C6") (pin "1") (pinfunction "1_1") (pintype "passive"))
      (node (ref "R_BOOT") (pin "2") (pinfunction "2_2") (pintype "passive"))
      (node (ref "U2") (pin "15") (pinfunction "IO9_15") (pintype "bidirectional"))
    )
    (net (code "18") (name "IO{slash}CHANGE") (class "Default")
      (node (ref "C10") (pin "1") (pinfunction "1_1") (pintype "passive"))
      (node (ref "CHANGE_BUTTON") (pin "3") (pinfunction "3_3") (pintype "passive"))
      (node (ref "CHANGE_BUTTON") (pin "4") (pinfunction "4_4") (pintype "passive"))
      (node (ref "R_CHANGE") (pin "2") (pinfunction "2_2") (pintype "passive"))
      (node (ref "U2") (pin "23") (pinfunction "IO15_23") (pintype "bidirectional"))
    )
    (net (code "19") (name "MISO") (class "Default")
      (node (ref "D12") (pin "1") (pinfunction "1_1") (pintype "passive"))
      (node (ref "J4") (pin "P7") (pinfunction "DAT0_P7") (pintype "bidirectional"))
      (node (ref "R8") (pin "1") (pinfunction "1_1") (pintype "passive"))
      (node (ref "TP6") (pin "TP") (pinfunction "TP_TP") (pintype "input"))
      (node (ref "U1") (pin "2") (pinfunction "DO(IO1)_2") (pintype "bidirectional"))
      (node (ref "U2") (pin "27") (pinfunction "IO2_27") (pintype "bidirectional"))
    )
    (net (code "20") (name "MOSI") (class "Default")
      (node (ref "D11") (pin "1") (pinfunction "1_1") (pintype "passive"))
      (node (ref "J1") (pin "14") (pinfunction "14_14") (pintype "bidirectional"))
      (node (ref "J4") (pin "P3") (pinfunction "CMD_P3") (pintype "bidirectional"))
      (node (ref "R7") (pin "1") (pinfunction "1_1") (pintype "passive"))
      (node (ref "TP7") (pin "TP") (pinfunction "TP_TP") (pintype "input"))
      (node (ref "U1") (pin "5") (pinfunction "DI(IO0)_5") (pintype "bidirectional"))
      (node (ref "U2") (pin "7") (pinfunction "IO7_7") (pintype "bidirectional"))
    )
    (net (code "21") (name "Net-(CHG_LED-PadC)") (class "Default")
      (node (ref "CHG_LED") (pin "C") (pinfunction "C_C") (pintype "passive"))
      (node (ref "R1_BAT") (pin "2") (pinfunction "2_2") (pintype "passive"))
    )
    (net (code "22") (name "Net-(D2-CATHODE)") (class "Default")
      (node (ref "C1_BAT1") (pin "1") (pinfunction "1_1") (pintype "passive"))
      (node (ref "D2") (pin "1") (pinfunction "CATHODE_1") (pintype "bidirectional"))
      (node (ref "IC4") (pin "1") (pinfunction "VIN_1") (pintype "bidirectional"))
      (node (ref "IC4") (pin "3") (pinfunction "CE_3") (pintype "bidirectional"))
      (node (ref "Q1") (pin "2") (pinfunction "S_2") (pintype "bidirectional"))
    )
    (net (code "23") (name "Net-(D3-A)") (class "Default")
      (node (ref "C4") (pin "1") (pinfunction "1_1") (pintype "passive"))
      (node (ref "D3") (pin "2") (pinfunction "A_2") (pintype "bidirectional"))
      (node (ref "D4") (pin "1") (pinfunction "K_1") (pintype "bidirectional"))
    )
    (net (code "24") (name "Net-(D7-CATHODE)") (class "Default")
      (node (ref "D7") (pin "1") (pinfunction "CATHODE_1") (pintype "bidirectional"))
      (node (ref "R_CAPACITOR") (pin "2") (pinfunction "2_2") (pintype "passive"))
    )
    (net (code "25") (name "Net-(EPD_C1-Pad1)") (class "Default")
      (node (ref "EPD_C1") (pin "1") (pinfunction "1_1") (pintype "passive"))
      (node (ref "J1") (pin "4") (pinfunction "4_4") (pintype "bidirectional"))
    )
    (net (code "26") (name "Net-(EPD_C2-Pad1)") (class "Default")
      (node (ref "EPD_C2") (pin "1") (pinfunction "1_1") (pintype "passive"))
      (node (ref "J1") (pin "5") (pinfunction "5_5") (pintype "bidirectional"))
    )
    (net (code "27") (name "Net-(EPD_C6-Pad1)") (class "Default")
      (node (ref "EPD_C6") (pin "1") (pinfunction "1_1") (pintype "passive"))
      (node (ref "J1") (pin "18") (pinfunction "18_18") (pintype "bidirectional"))
    )
    (net (code "28") (name "Net-(EPD_C7-Pad1)") (class "Default")
      (node (ref "EPD_C7") (pin "1") (pinfunction "1_1") (pintype "passive"))
      (node (ref "J1") (pin "19") (pinfunction "19_19") (pintype "bidirectional"))
    )
    (net (code "29") (name "Net-(EPD_C8-Pad1)") (class "Default")
      (node (ref "EPD_C8") (pin "1") (pinfunction "1_1") (pintype "passive"))
      (node (ref "J1") (pin "20") (pinfunction "20_20") (pintype "bidirectional"))
    )
    (net (code "30") (name "Net-(EPD_C10-Pad1)") (class "Default")
      (node (ref "EPD_C10") (pin "1") (pinfunction "1_1") (pintype "passive"))
      (node (ref "J1") (pin "22") (pinfunction "22_22") (pintype "bidirectional"))
    )
    (net (code "31") (name "Net-(EPD_C12-Pad1)") (class "Default")
      (node (ref "EPD_C12") (pin "1") (pinfunction "1_1") (pintype "passive"))
      (node (ref "J1") (pin "24") (pinfunction "24_24") (pintype "bidirectional"))
    )
    (net (code "32") (name "Net-(IC1-CT)") (class "Default")
      (node (ref "C_DELAY") (pin "1") (pinfunction "1_1") (pintype "passive"))
      (node (ref "IC1") (pin "5") (pinfunction "CT_5") (pintype "bidirectional"))
    )
    (net (code "33") (name "Net-(J2-PadA5)") (class "Default")
      (node (ref "J2") (pin "A5") (pinfunction "A5_A5") (pintype "bidirectional"))
      (node (ref "R2-USB1") (pin "2") (pinfunction "2_2") (pintype "passive"))
    )
    (net (code "34") (name "Net-(J2-PadB5)") (class "Default")
      (node (ref "J2") (pin "B5") (pinfunction "B5_B5") (pintype "bidirectional"))
      (node (ref "R2-USB") (pin "1") (pinfunction "1_1") (pintype "passive"))
    )
    (net (code "35") (name "Net-(U5-PROG)") (class "Default")
      (node (ref "R2_BAT") (pin "2") (pinfunction "2_2") (pintype "passive"))
      (node (ref "U5") (pin "5") (pinfunction "PROG_5") (pintype "input"))
    )
    (net (code "36") (name "Net-(U5-STAT)") (class "Default")
      (node (ref "R1_BAT") (pin "1") (pinfunction "1_1") (pintype "passive"))
      (node (ref "U5") (pin "1") (pinfunction "STAT_1") (pintype "output"))
    )
    (net (code "37") (name "PREVGH") (class "Default")
      (node (ref "D5") (pin "1") (pinfunction "K_1") (pintype "bidirectional"))
      (node (ref "EPD_C9") (pin "1") (pinfunction "1_1") (pintype "passive"))
      (node (ref "J1") (pin "21") (pinfunction "21_21") (pintype "bidirectional"))
    )
    (net (code "38") (name "PREVGL") (class "Default")
      (node (ref "D4") (pin "2") (pinfunction "A_2") (pintype "bidirectional"))
      (node (ref "EPD_C11") (pin "1") (pinfunction "1_1") (pintype "passive"))
      (node (ref "J1") (pin "23") (pinfunction "23_23") (pintype "bidirectional"))
    )
    (net (code "39") (name "RESE") (class "Default")
      (node (ref "J1") (pin "3") (pinfunction "3_3") (pintype "bidirectional"))
      (node (ref "Q3") (pin "2") (pinfunction "S_2") (pintype "bidirectional"))
      (node (ref "R3") (pin "1") (pinfunction "1_1") (pintype "passive"))
    )
    (net (code "40") (name "RESE'") (class "Default")
      (node (ref "R2") (pin "2") (pinfunction "2_2") (pintype "passive"))
      (node (ref "R3") (pin "2") (pinfunction "2_2") (pintype "passive"))
      (node (ref "SJ1") (pin "2") (pinfunction "2_2") (pintype "passive"))
    )
    (net (code "41") (name "RESET") (class "Default")
      (node (ref "C5") (pin "1") (pinfunction "1_1") (pintype "passive"))
      (node (ref "IC1") (pin "1") (pinfunction "VOUT_1") (pintype "bidirectional"))
      (node (ref "RESET_BUTTON") (pin "3") (pinfunction "3_3") (pintype "passive"))
      (node (ref "RESET_BUTTON") (pin "4") (pinfunction "4_4") (pintype "passive"))
      (node (ref "R_RESET") (pin "2") (pinfunction "2_2") (pintype "passive"))
      (node (ref "U2") (pin "3") (pinfunction "EN_3") (pintype "input"))
    )
    (net (code "42") (name "RTC_RST") (class "Default")
      (node (ref "U2") (pin "16") (pinfunction "IO18_16") (pintype "bidirectional"))
      (node (ref "U3") (pin "4") (pinfunction "~{RST}_4") (pintype "input"))
    )
    (net (code "43") (name "RX") (class "Default")
      (node (ref "TP2") (pin "TP") (pinfunction "TP_TP") (pintype "input"))
      (node (ref "U2") (pin "24") (pinfunction "RXD0/GPIO17_24") (pintype "bidirectional"))
    )
    (net (code "44") (name "SCK") (class "Default")
      (node (ref "D10") (pin "1") (pinfunction "1_1") (pintype "passive"))
      (node (ref "J1") (pin "13") (pinfunction "13_13") (pintype "bidirectional"))
      (node (ref "J4") (pin "P5") (pinfunction "CLK_P5") (pintype "bidirectional"))
      (node (ref "R6") (pin "1") (pinfunction "1_1") (pintype "passive"))
      (node (ref "TP8") (pin "TP") (pinfunction "TP_TP") (pintype "input"))
      (node (ref "U1") (pin "6") (pinfunction "CLK_6") (pintype "input"))
      (node (ref "U2") (pin "6") (pinfunction "IO6_6") (pintype "bidirectional"))
    )
    (net (code "45") (name "SCL") (class "Default")
      (node (ref "J3") (pin "4") (pinfunction "4_4") (pintype "passive"))
      (node (ref "R2_PINH") (pin "1") (pinfunction "1_1") (pintype "passive"))
      (node (ref "SENSOR2") (pin "4") (pinfunction "SCK_4") (pintype "input"))
      (node (ref "U2") (pin "20") (pinfunction "IO22_20") (pintype "bidirectional"))
      (node (ref "U3") (pin "16") (pinfunction "SCL_16") (pintype "input"))
      (node (ref "U4") (pin "7") (pinfunction "SCL_7") (pintype "input"))
    )
    (net (code "46") (name "SDA") (class "Default")
      (node (ref "J3") (pin "3") (pinfunction "3_3") (pintype "passive"))
      (node (ref "R1_PINH") (pin "1") (pinfunction "1_1") (pintype "passive"))
      (node (ref "SENSOR2") (pin "3") (pinfunction "SDI_3") (pintype "bidirectional"))
      (node (ref "U2") (pin "19") (pinfunction "IO21_19") (pintype "bidirectional"))
      (node (ref "U3") (pin "15") (pinfunction "SDA_15") (pintype "bidirectional"))
      (node (ref "U4") (pin "8") (pinfunction "SDA_8") (pintype "bidirectional"))
    )
    (net (code "47") (name "SRC") (class "Default")
      (node (ref "C4") (pin "2") (pinfunction "2_2") (pintype "passive"))
      (node (ref "D5") (pin "2") (pinfunction "A_2") (pintype "bidirectional"))
      (node (ref "L1") (pin "1") (pinfunction "1_1") (pintype "passive"))
      (node (ref "Q3") (pin "3") (pinfunction "D_3") (pintype "bidirectional"))
    )
    (net (code "48") (name "SS_SD") (class "Default")
      (node (ref "D8") (pin "1") (pinfunction "1_1") (pintype "passive"))
      (node (ref "J4") (pin "P2") (pinfunction "CD/DAT3_P2") (pintype "bidirectional"))
      (node (ref "R10") (pin "1") (pinfunction "1_1") (pintype "passive"))
      (node (ref "U2") (pin "4") (pinfunction "IO4_4") (pintype "bidirectional"))
    )
    (net (code "49") (name "TX") (class "Default")
      (node (ref "TP1") (pin "TP") (pinfunction "TP_TP") (pintype "input"))
      (node (ref "U2") (pin "25") (pinfunction "TXD0/GPIO16_25") (pintype "bidirectional"))
    )
    (net (code "50") (name "USB_D+") (class "Default")
      (node (ref "D1") (pin "1") (pinfunction "I/O1_1_1") (pintype "bidirectional"))
      (node (ref "U2") (pin "14") (pinfunction "IO13_14") (pintype "bidirectional"))
    )
    (net (code "51") (name "USB_D-") (class "Default")
      (node (ref "D1") (pin "3") (pinfunction "I/O2_1_3") (pintype "bidirectional"))
      (node (ref "U2") (pin "13") (pinfunction "IO12_13") (pintype "bidirectional"))
    )
    (net (code "52") (name "VBAT") (class "Default")
      (node (ref "C2_BAT") (pin "1") (pinfunction "1_1") (pintype "passive"))
      (node (ref "Q1") (pin "3") (pinfunction "D_3") (pintype "bidirectional"))
      (node (ref "TP3") (pin "TP") (pinfunction "TP_TP") (pintype "input"))
      (node (ref "U4") (pin "2") (pinfunction "CELL_2") (pintype "power_in"))
      (node (ref "U4") (pin "3") (pinfunction "VDD_3") (pintype "power_in"))
      (node (ref "U5") (pin "3") (pinfunction "VBAT_3") (pintype "power_in"))
    )
    (net (code "53") (name "VBUS") (class "Default")
      (node (ref "C1_BAT") (pin "1") (pinfunction "1_1") (pintype "passive"))
      (node (ref "C4_USB") (pin "1") (pinfunction "1_1") (pintype "passive"))
      (node (ref "C5_USB") (pin "1") (pinfunction "1_1") (pintype "passive"))
      (node (ref "CHG_LED") (pin "A") (pinfunction "A_A") (pintype "passive"))
      (node (ref "D1") (pin "5") (pinfunction "VBUS_5") (pintype "bidirectional"))
      (node (ref "D2") (pin "2") (pinfunction "ANODE_2") (pintype "bidirectional"))
      (node (ref "PFMF.050.1") (pin "2") (pinfunction "2_2") (pintype "passive"))
      (node (ref "Q1") (pin "1") (pinfunction "G_1") (pintype "bidirectional"))
      (node (ref "R1_PWRUSB") (pin "2") (pinfunction "2_2") (pintype "passive"))
      (node (ref "TP14") (pin "TP") (pinfunction "TP_TP") (pintype "input"))
      (node (ref "U5") (pin "4") (pinfunction "VIN_4") (pintype "power_in"))
    )
    (net (code "54") (name "VRTC") (class "Default")
      (node (ref "C10_SUPERCAP") (pin "2") (pinfunction "2_2") (pintype "passive"))
      (node (ref "C8") (pin "1") (pinfunction "1_1") (pintype "passive"))
      (node (ref "R_CAPACITOR") (pin "1") (pinfunction "1_1") (pintype "passive"))
      (node (ref "U3") (pin "14") (pinfunction "VBAT_14") (pintype "power_in"))
    )
    (net (code "55") (name "VUSB") (class "Default")
      (node (ref "J2") (pin "A4") (pinfunction "A4_A4") (pintype "bidirectional"))
      (node (ref "J2") (pin "A9") (pinfunction "A9_A9") (pintype "bidirectional"))
      (node (ref "J2") (pin "B4") (pinfunction "B4_B4") (pintype "bidirectional"))
      (node (ref "J2") (pin "B9") (pinfunction "B9_B9") (pintype "bidirectional"))
      (node (ref "PFMF.050.1") (pin "1") (pinfunction "1_1") (pintype "passive"))
    )
    (net (code "56") (name "unconnected-(IC1-NC-Pad4)") (class "Default")
      (node (ref "IC1") (pin "4") (pinfunction "NC_4") (pintype "no_connect"))
    )
    (net (code "57") (name "unconnected-(IC4-NC-Pad4)") (class "Default")
      (node (ref "IC4") (pin "4") (pinfunction "NC_4") (pintype "no_connect"))
    )
    (net (code "58") (name "unconnected-(J1-Pad1)") (class "Default")
      (node (ref "J1") (pin "1") (pinfunction "1_1") (pintype "bidirectional"))
    )
    (net (code "59") (name "unconnected-(J1-Pad6)") (class "Default")
      (node (ref "J1") (pin "6") (pinfunction "6_6") (pintype "bidirectional"))
    )
    (net (code "60") (name "unconnected-(J1-Pad7)") (class "Default")
      (node (ref "J1") (pin "7") (pinfunction "7_7") (pintype "bidirectional"))
    )
    (net (code "61") (name "unconnected-(J2-PadA8)") (class "Default")
      (node (ref "J2") (pin "A8") (pinfunction "A8_A8") (pintype "bidirectional"))
    )
    (net (code "62") (name "unconnected-(J2-PadB8)") (class "Default")
      (node (ref "J2") (pin "B8") (pinfunction "B8_B8") (pintype "bidirectional"))
    )
    (net (code "63") (name "unconnected-(J4-DAT1-PadP8)") (class "Default")
      (node (ref "J4") (pin "P8") (pinfunction "DAT1_P8") (pintype "bidirectional"))
    )
    (net (code "64") (name "unconnected-(J4-DAT2-PadP1)") (class "Default")
      (node (ref "J4") (pin "P1") (pinfunction "DAT2_P1") (pintype "bidirectional"))
    )
    (net (code "65") (name "unconnected-(J4-DETECTION_1-PadS1)") (class "Default")
      (node (ref "J4") (pin "S1") (pinfunction "DETECTION_1_S1") (pintype "bidirectional"))
    )
    (net (code "66") (name "unconnected-(J4-DETECTION_2-PadS2)") (class "Default")
      (node (ref "J4") (pin "S2") (pinfunction "DETECTION_2_S2") (pintype "bidirectional"))
    )
    (net (code "67") (name "unconnected-(U2-NC-Pad22)") (class "Default")
      (node (ref "U2") (pin "22") (pinfunction "NC_22") (pintype "no_connect"))
    )
    (net (code "68") (name "unconnected-(U4-~{ALERT}-Pad5)") (class "Default")
      (node (ref "U4") (pin "5") (pinfunction "~{ALERT}_5") (pintype "output"))
    )
  )
)
